# Powering.net
KiCad netlist of a schematic drawn in Altium Designer
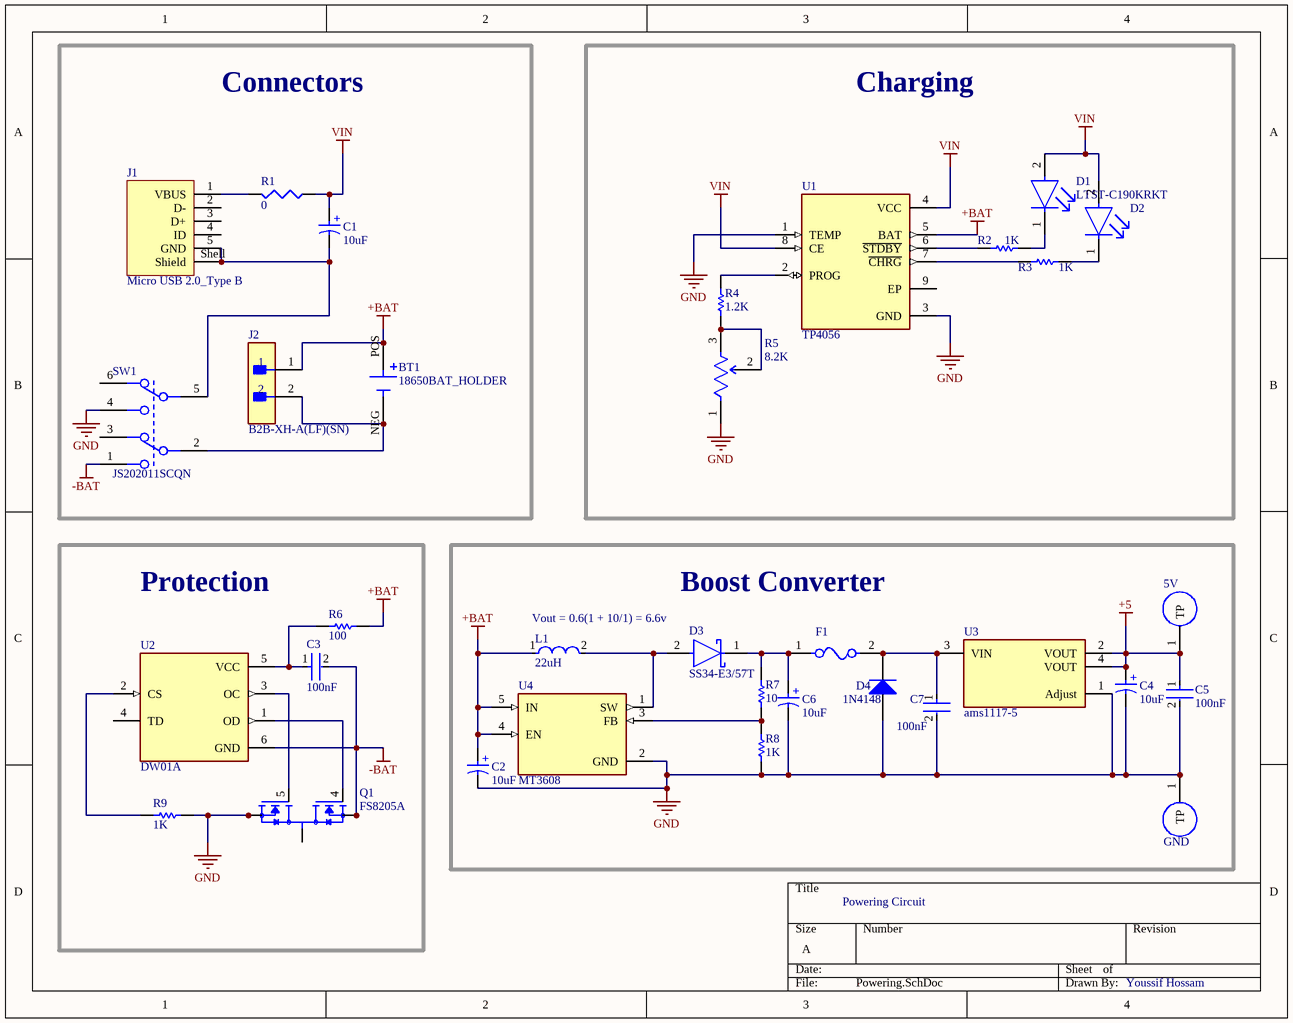
[diagram p0: Powering.SchDoc]

(export (version "E")
  (design (tool "Eeschema 10.0.6"))
  (components
    (comp (ref "5V")
      (value "Test Point")
      (footprint "Test_Point")
      (libsource (lib "YoussifLIB") (part "Test Point"))
    )
    (comp (ref "BT1")
      (value "18650BAT_HOLDER")
      (footprint "18650BAT_HOLDER")
      (description "Battery Holder (Open) 18650 1 Cell PC Pin")
      (fields (field (name "MP") "BK-18650-PC2"))
      (libsource (lib "YoussifLIB") (part "18650BAT_HOLDER"))
    )
    (comp (ref "C1")
      (value "10uF")
      (footprint "WCAP-ASLU_D3H5.5")
      (description "WCAP-ASLU Aluminum Electrolytic Capacitor, V-Chip, D4 x H5.5mm, 10uF, 6.3V")
      (fields
        (field (name "MANUFACTURER PART NUMBER") "865090140001")
        (field (name "MANUFACTURER") "Wurth Elektronik")
      )
      (libsource (lib "YoussifLIB") (part "WCAP-ASLU_D3H5.5"))
    )
    (comp (ref "C2")
      (value "10uF")
      (footprint "WCAP-ASLU_D3H5.5")
      (description "WCAP-ASLU Aluminum Electrolytic Capacitor, V-Chip, D4 x H5.5mm, 10uF, 6.3V")
      (fields
        (field (name "MANUFACTURER PART NUMBER") "865090140001")
        (field (name "MANUFACTURER") "Wurth Elektronik")
      )
      (libsource (lib "YoussifLIB") (part "WCAP-ASLU_D3H5.5"))
    )
    (comp (ref "C3")
      (value "100nF")
      (footprint "FP-C0402-BB-MFG")
      (description "CAP CER 0.1UF 10V X5R 0402")
      (fields (field (name "MANUFACTURER") "Kemet") (field (name "TOLERANCE") "0.1"))
      (libsource (lib "Altium Content Vault") (part "b4654b650e69147ec39a6b967a45e02"))
    )
    (comp (ref "C4")
      (value "10uF")
      (footprint "WCAP-ASLU_D3H5.5")
      (description "WCAP-ASLU Aluminum Electrolytic Capacitor, V-Chip, D4 x H5.5mm, 10uF, 6.3V")
      (fields
        (field (name "MANUFACTURER PART NUMBER") "865090140001")
        (field (name "MANUFACTURER") "Wurth Elektronik")
      )
      (libsource (lib "YoussifLIB") (part "WCAP-ASLU_D3H5.5"))
    )
    (comp (ref "C5")
      (value "100nF")
      (footprint "FP-CGA3E-0_3-0_1-IPC_A")
      (description "Cap Ceramic 100nF 50V X7R 10% Pad SMD 0603 +125°C Automotive T/R")
      (fields (field (name "TOLERANCE") "10%") (field (name "VOLTAGE") "50V"))
      (libsource (lib "Altium Content Vault") (part "b4654b650e69147ec39a6b967a45e02"))
    )
    (comp (ref "C6")
      (value "10uF")
      (footprint "WCAP-ASLU_D3H5.5")
      (description "WCAP-ASLU Aluminum Electrolytic Capacitor, V-Chip, D4 x H5.5mm, 10uF, 6.3V")
      (fields
        (field (name "MANUFACTURER PART NUMBER") "865090140001")
        (field (name "MANUFACTURER") "Wurth Elektronik")
      )
      (libsource (lib "YoussifLIB") (part "WCAP-ASLU_D3H5.5"))
    )
    (comp (ref "C7")
      (value "100nF")
      (footprint "FP-CGA3E-0_3-0_1-IPC_A")
      (description "Cap Ceramic 100nF 50V X7R 10% Pad SMD 0603 +125°C Automotive T/R")
      (fields (field (name "TOLERANCE") "10%") (field (name "VOLTAGE") "50V"))
      (libsource (lib "Altium Content Vault") (part "b4654b650e69147ec39a6b967a45e02"))
    )
    (comp (ref "D1")
      (value "LTST-C190KRKT")
      (footprint "FP-LTST-C190KRKT-MFG")
      (description "LED RED CLEAR CHIP SMD")
      (libsource (lib "Altium Content Vault") (part "8706943c75ba83719d021d2fdc84c58"))
    )
    (comp (ref "D2")
      (value "LTST-C190GKT")
      (footprint "FP-LTST-C190GKT-MFG")
      (description "LED GREEN CLEAR CHIP SMD")
      (fields (field (name "VOLTAGE") "2V"))
      (libsource (lib "Altium Content Vault") (part "8706943c75ba83719d021d2fdc84c58"))
    )
    (comp (ref "D3")
      (value "SS34-E3/57T")
      (footprint "FP-95402-MFG")
      (description "DIODE SCHOTTKY 40V 3A DO214AB")
      (fields
        (field (name "MANUFACTURER") "Vishay")
        (field (name "OCTOPART") "https://octopart.com/ss34-e3%2F57t-vishay-39552907")
      )
      (libsource (lib "Altium Content Vault") (part "1d6ec82d83fb6aee721767c19dac4b9"))
    )
    (comp (ref "D4")
      (value "1N4148")
      (footprint "DIOD-SOD123-2_V")
      (description "Fast Switching Diode, 100 V, 0.15 A, -65 to 150 degC, 2-Pin?SOD123, RoHS, Tape and Reel")
      (fields (field (name "MANUFACTURER") "DiodesIncorporated"))
      (libsource (lib "Altium Content Vault") (part "D-AK-2"))
    )
    (comp (ref "F1")
      (value "0154004.DR")
      (footprint "FP-0154-MFG")
      (description "FUSE BRD MNT 4A 125VAC/VDC 2SMD")
      (fields
        (field (name "MANUFACTURER") "Littelfuse")
        (field (name "OCTOPART") "https://octopart.com/0154004.dr-littelfuse-565861")
      )
      (libsource (lib "Altium Content Vault") (part "5bcf9b9f640e542cf0359d10258e979"))
    )
    (comp (ref "GND")
      (value "Test Point")
      (footprint "Test_Point")
      (libsource (lib "YoussifLIB") (part "Test Point"))
    )
    (comp (ref "J1")
      (value "Micro USB 2.0_Type B")
      (footprint "Micro USB 2.0_Type B")
      (libsource (lib "YoussifLIB") (part "Micro USB 2.0_Type B"))
    )
    (comp (ref "J2")
      (value "B2B-XH-A(LF)(SN)")
      (footprint "FP-B2B-XH-A_LF_SN-MFG")
      (description "CONN HEADER VERT 2POS 2.5MM")
      (libsource (lib "Altium Content Vault") (part "3bc925449376181038e59eaffc5286c"))
    )
    (comp (ref "L1")
      (value "22uH")
      (footprint "FP-IHLP-2525CZ-FP_2_413x3-MFG")
      (description "Commercial Inductors, Low DCR Series 22uH 2.9A 135mΩ 20%")
      (fields (field (name "TOLERANCE") "20%"))
      (libsource (lib "Altium Content Vault") (part "725321dda6339637d4d059423bc1c3c"))
    )
    (comp (ref "Q1")
      (value "FS8205A")
      (footprint "SOP65P640X120-8N")
      (fields (field (name "MF") "Fortune Semiconductor"))
      (libsource (lib "YoussifLIB") (part "FS8205A"))
    )
    (comp (ref "R1")
      (value "0")
      (footprint "J1-0603")
      (description "Resistor")
      (fields (field (name "PUBLISHER") "Altium Limited"))
      (libsource (lib "Miscellaneous+Devices") (part "Res3"))
    )
    (comp (ref "R2")
      (value "1K")
      (footprint "RESC1005X40X25NL05T10")
      (fields (field (name "MANUFACTURER") "Yageo / Phycomp") (field (name "PART NUMBER") "RC0402JR-070RL"))
      (libsource (lib "Altium Content Vault") (part "RES"))
    )
    (comp (ref "R3")
      (value "1K")
      (footprint "RESC1005X40X25NL05T10")
      (fields (field (name "MANUFACTURER") "Yageo / Phycomp") (field (name "PART NUMBER") "RC0402JR-070RL"))
      (libsource (lib "Altium Content Vault") (part "RES"))
    )
    (comp (ref "R4")
      (value "1.2K")
      (footprint "RESC1608X55X25ML10T15")
      (description "Chip Resistor, 0 Ohm, +/- 5%, 0.1 W, -55 to 155 degC, 0603 (1608 Metric), RoHS, Tape and Reel")
      (fields (field (name "TOLERANCE") "5%") (field (name "MANUFACTURER") "Yageo"))
      (libsource (lib "Altium Content Vault") (part "RES-2"))
    )
    (comp (ref "R5")
      (value "8.2K")
      (footprint "FP-TS53YL-MFG")
      (description "TRIMMER 10K OHM 0.25W GW TOP ADJ")
      (fields (field (name "TOLERANCE") "20%"))
      (libsource (lib "Altium Content Vault") (part "af6d6fb613c1f66b9b47f3e4c9350cb"))
    )
    (comp (ref "R6")
      (value "100")
      (footprint "RESC1005X40X25NL05T10")
      (fields (field (name "MANUFACTURER") "Yageo / Phycomp") (field (name "PART NUMBER") "RC0402JR-070RL"))
      (libsource (lib "Altium Content Vault") (part "RES"))
    )
    (comp (ref "R7")
      (value "10")
      (footprint "RESC1608X55X25ML10T15")
      (description "Chip Resistor, 0 Ohm, +/- 5%, 0.1 W, -55 to 155 degC, 0603 (1608 Metric), RoHS, Tape and Reel")
      (fields (field (name "TOLERANCE") "5%") (field (name "MANUFACTURER") "Yageo"))
      (libsource (lib "Altium Content Vault") (part "RES-2"))
    )
    (comp (ref "R8")
      (value "1K")
      (footprint "RESC1608X55X25ML10T15")
      (description "Chip Resistor, 0 Ohm, +/- 5%, 0.1 W, -55 to 155 degC, 0603 (1608 Metric), RoHS, Tape and Reel")
      (fields (field (name "TOLERANCE") "5%") (field (name "MANUFACTURER") "Yageo"))
      (libsource (lib "Altium Content Vault") (part "RES-2"))
    )
    (comp (ref "R9")
      (value "1K")
      (footprint "RESC1608X55X25ML10T15")
      (description "Chip Resistor, 0 Ohm, +/- 5%, 0.1 W, -55 to 155 degC, 0603 (1608 Metric), RoHS, Tape and Reel")
      (fields (field (name "TOLERANCE") "5%") (field (name "MANUFACTURER") "Yageo"))
      (libsource (lib "Altium Content Vault") (part "RES-2"))
    )
    (comp (ref "SW1")
      (value "JS202011SCQN")
      (footprint "FP-JS202011SCQN-MFG")
      (description "SWITCH SLIDE DPDT 300MA 6V")
      (libsource (lib "Altium Content Vault") (part "ac99ea1af431c19115f5225061c5c88"))
    )
    (comp (ref "U1")
      (value "TP4056")
      (footprint "TP4056")
      (description "Complete single cell Li-Ion battery with a constant current / constant voltage linear charger")
      (fields (field (name "MF") "NanJing Top Power ASIC Corp."))
      (libsource (lib "YoussifLIB") (part "TP4056"))
    )
    (comp (ref "U2")
      (value "DW01A")
      (footprint "SOT95P280X145-6N")
      (description "One Cell Lithium-ion/Polymer Battery Protection IC")
      (fields (field (name "MF") "Fortune Semiconductor"))
      (libsource (lib "YoussifLIB") (part "DW01A"))
    )
    (comp (ref "U3")
      (value "ams1117-5")
      (footprint "FP-ams1117-IPC_C")
      (description "1A LOW DROPOUT VOLTAGE REGULATOR")
      (libsource (lib "Altium Content Vault") (part "59ad430b93a2c51b3e6ee7c3b069677"))
    )
    (comp (ref "U4")
      (value "MT3608")
      (footprint "SOT95P280X145-6N")
      (description "High Efficiency 1.2MHz2A Step Up Converter")
      (fields (field (name "MF") "Aerosemi Technology Co., Ltd"))
      (libsource (lib "YoussifLIB") (part "MT3608"))
    )
  )
  (nets
    (net (code "1") (name "+5") (class "Default")
      (node (ref "5V") (pin "1") (pinfunction "TP_1") (pintype "passive"))
      (node (ref "C4") (pin "1") (pinfunction "P_1") (pintype "passive"))
      (node (ref "C5") (pin "1") (pinfunction "1_1") (pintype "passive"))
      (node (ref "U3") (pin "2") (pinfunction "VOUT_2") (pintype "passive"))
      (node (ref "U3") (pin "4") (pinfunction "VOUT_4") (pintype "passive"))
    )
    (net (code "2") (name "+BAT") (class "Default")
      (node (ref "BT1") (pin "POS") (pinfunction "POS_POS") (pintype "passive"))
      (node (ref "C2") (pin "1") (pinfunction "P_1") (pintype "passive"))
      (node (ref "J2") (pin "1") (pinfunction "1_1") (pintype "passive"))
      (node (ref "L1") (pin "1") (pinfunction "1_1") (pintype "passive"))
      (node (ref "R6") (pin "2") (pinfunction "2_2") (pintype "passive"))
      (node (ref "U1") (pin "5") (pinfunction "BAT_5") (pintype "output"))
      (node (ref "U4") (pin "4") (pinfunction "EN_4") (pintype "input"))
      (node (ref "U4") (pin "5") (pinfunction "IN_5") (pintype "input"))
    )
    (net (code "3") (name "-BAT") (class "Default")
      (node (ref "C3") (pin "2") (pinfunction "2_2") (pintype "passive"))
      (node (ref "Q1") (pin "2") (pinfunction "S1_2") (pintype "passive"))
      (node (ref "Q1") (pin "3") (pinfunction "S1_3") (pintype "passive"))
      (node (ref "SW1") (pin "1") (pinfunction "1_1") (pintype "passive"))
      (node (ref "U2") (pin "6") (pinfunction "GND_6") (pintype "power_in"))
    )
    (net (code "4") (name "GND") (class "Default")
      (node (ref "C2") (pin "2") (pinfunction "N_2") (pintype "passive"))
      (node (ref "C4") (pin "2") (pinfunction "N_2") (pintype "passive"))
      (node (ref "C5") (pin "2") (pinfunction "2_2") (pintype "passive"))
      (node (ref "C6") (pin "2") (pinfunction "N_2") (pintype "passive"))
      (node (ref "C7") (pin "2") (pinfunction "2_2") (pintype "passive"))
      (node (ref "D4") (pin "1") (pinfunction "A_1") (pintype "passive"))
      (node (ref "GND") (pin "1") (pinfunction "TP_1") (pintype "passive"))
      (node (ref "Q1") (pin "6") (pinfunction "S2_6") (pintype "passive"))
      (node (ref "Q1") (pin "7") (pinfunction "S2_7") (pintype "passive"))
      (node (ref "R5") (pin "1") (pinfunction "a_1") (pintype "passive"))
      (node (ref "R8") (pin "1") (pinfunction "1_1") (pintype "passive"))
      (node (ref "R9") (pin "2") (pinfunction "2_2") (pintype "passive"))
      (node (ref "SW1") (pin "4") (pinfunction "4_4") (pintype "passive"))
      (node (ref "U1") (pin "1") (pinfunction "TEMP_1") (pintype "input"))
      (node (ref "U1") (pin "3") (pinfunction "GND_3") (pintype "power_in"))
      (node (ref "U3") (pin "1") (pinfunction "Adjust_1") (pintype "passive"))
      (node (ref "U4") (pin "2") (pinfunction "GND_2") (pintype "power_in"))
    )
    (net (code "5") (name "Net-(BT1-PadNEG)") (class "Default")
      (node (ref "BT1") (pin "NEG") (pinfunction "NEG_NEG") (pintype "passive"))
      (node (ref "J2") (pin "2") (pinfunction "2_2") (pintype "passive"))
      (node (ref "SW1") (pin "2") (pinfunction "2_2") (pintype "passive"))
    )
    (net (code "6") (name "Net-(C1-N)") (class "Default")
      (node (ref "C1") (pin "2") (pinfunction "N_2") (pintype "passive"))
      (node (ref "J1") (pin "5") (pinfunction "GND_5") (pintype "passive"))
      (node (ref "J1") (pin "Shell") (pinfunction "Shield_Shell") (pintype "passive"))
      (node (ref "SW1") (pin "5") (pinfunction "5_5") (pintype "passive"))
    )
    (net (code "7") (name "Net-(C6-P)") (class "Default")
      (node (ref "C6") (pin "1") (pinfunction "P_1") (pintype "passive"))
      (node (ref "D3") (pin "1") (pinfunction "C_1") (pintype "passive"))
      (node (ref "F1") (pin "1") (pinfunction "1_1") (pintype "passive"))
      (node (ref "R7") (pin "2") (pinfunction "2_2") (pintype "passive"))
    )
    (net (code "8") (name "Net-(D1-C)") (class "Default")
      (node (ref "D1") (pin "1") (pinfunction "C_1") (pintype "passive"))
      (node (ref "R2") (pin "2") (pinfunction "2_2") (pintype "passive"))
    )
    (net (code "9") (name "Net-(D2-C)") (class "Default")
      (node (ref "D2") (pin "1") (pinfunction "C_1") (pintype "passive"))
      (node (ref "R3") (pin "2") (pinfunction "2_2") (pintype "passive"))
    )
    (net (code "10") (name "Net-(D3-A)") (class "Default")
      (node (ref "D3") (pin "2") (pinfunction "A_2") (pintype "passive"))
      (node (ref "L1") (pin "2") (pinfunction "2_2") (pintype "passive"))
      (node (ref "U4") (pin "1") (pinfunction "SW_1") (pintype "output"))
    )
    (net (code "11") (name "Net-(D4-K)") (class "Default")
      (node (ref "C7") (pin "1") (pinfunction "1_1") (pintype "passive"))
      (node (ref "D4") (pin "2") (pinfunction "K_2") (pintype "passive"))
      (node (ref "F1") (pin "2") (pinfunction "2_2") (pintype "passive"))
      (node (ref "U3") (pin "3") (pinfunction "VIN_3") (pintype "power_in"))
    )
    (net (code "12") (name "Net-(J1-VBUS)") (class "Default")
      (node (ref "J1") (pin "1") (pinfunction "VBUS_1") (pintype "passive"))
      (node (ref "R1") (pin "2") (pinfunction "2_2") (pintype "passive"))
    )
    (net (code "13") (name "Net-(Q1-D12-Pad1)") (class "Default")
      (node (ref "Q1") (pin "1") (pinfunction "D12_1") (pintype "passive"))
      (node (ref "Q1") (pin "8") (pinfunction "D12_8") (pintype "passive"))
    )
    (net (code "14") (name "Net-(Q1-G1)") (class "Default")
      (node (ref "Q1") (pin "4") (pinfunction "G1_4") (pintype "passive"))
      (node (ref "U2") (pin "1") (pinfunction "OD_1") (pintype "output"))
    )
    (net (code "15") (name "Net-(Q1-G2)") (class "Default")
      (node (ref "Q1") (pin "5") (pinfunction "G2_5") (pintype "passive"))
      (node (ref "U2") (pin "3") (pinfunction "OC_3") (pintype "output"))
    )
    (net (code "16") (name "Net-(R5-b)") (class "Default")
      (node (ref "R4") (pin "1") (pinfunction "1_1") (pintype "passive"))
      (node (ref "R5") (pin "2") (pinfunction "b_2") (pintype "passive"))
      (node (ref "R5") (pin "3") (pinfunction "c_3") (pintype "passive"))
    )
    (net (code "17") (name "Net-(U1-PROG)") (class "Default")
      (node (ref "R4") (pin "2") (pinfunction "2_2") (pintype "passive"))
      (node (ref "U1") (pin "2") (pinfunction "PROG_2") (pintype "bidirectional"))
    )
    (net (code "18") (name "Net-(U1-~{CHRG})") (class "Default")
      (node (ref "R3") (pin "1") (pinfunction "1_1") (pintype "passive"))
      (node (ref "U1") (pin "7") (pinfunction "~{CHRG}_7") (pintype "output"))
    )
    (net (code "19") (name "Net-(U1-~{STDBY})") (class "Default")
      (node (ref "R2") (pin "1") (pinfunction "1_1") (pintype "passive"))
      (node (ref "U1") (pin "6") (pinfunction "~{STDBY}_6") (pintype "output"))
    )
    (net (code "20") (name "Net-(U2-CS)") (class "Default")
      (node (ref "R9") (pin "1") (pinfunction "1_1") (pintype "passive"))
      (node (ref "U2") (pin "2") (pinfunction "CS_2") (pintype "input"))
    )
    (net (code "21") (name "Net-(U2-VCC)") (class "Default")
      (node (ref "C3") (pin "1") (pinfunction "1_1") (pintype "passive"))
      (node (ref "R6") (pin "1") (pinfunction "1_1") (pintype "passive"))
      (node (ref "U2") (pin "5") (pinfunction "VCC_5") (pintype "power_in"))
    )
    (net (code "22") (name "Net-(U4-FB)") (class "Default")
      (node (ref "R7") (pin "1") (pinfunction "1_1") (pintype "passive"))
      (node (ref "R8") (pin "2") (pinfunction "2_2") (pintype "passive"))
      (node (ref "U4") (pin "3") (pinfunction "FB_3") (pintype "input"))
    )
    (net (code "23") (name "VIN") (class "Default")
      (node (ref "C1") (pin "1") (pinfunction "P_1") (pintype "passive"))
      (node (ref "D1") (pin "2") (pinfunction "A_2") (pintype "passive"))
      (node (ref "D2") (pin "2") (pinfunction "A_2") (pintype "passive"))
      (node (ref "R1") (pin "1") (pinfunction "1_1") (pintype "passive"))
      (node (ref "U1") (pin "4") (pinfunction "VCC_4") (pintype "power_in"))
      (node (ref "U1") (pin "8") (pinfunction "CE_8") (pintype "input"))
    )
    (net (code "24") (name "unconnected-(J1-D+-Pad3)") (class "Default")
      (node (ref "J1") (pin "3") (pinfunction "D+_3") (pintype "passive"))
    )
    (net (code "25") (name "unconnected-(J1-D--Pad2)") (class "Default")
      (node (ref "J1") (pin "2") (pinfunction "D-_2") (pintype "passive"))
    )
    (net (code "26") (name "unconnected-(J1-ID-Pad4)") (class "Default")
      (node (ref "J1") (pin "4") (pinfunction "ID_4") (pintype "passive"))
    )
    (net (code "27") (name "unconnected-(SW1-Pad3)") (class "Default")
      (node (ref "SW1") (pin "3") (pinfunction "3_3") (pintype "passive"))
    )
    (net (code "28") (name "unconnected-(SW1-Pad6)") (class "Default")
      (node (ref "SW1") (pin "6") (pinfunction "6_6") (pintype "passive"))
    )
    (net (code "29") (name "unconnected-(U1-EP-Pad9)") (class "Default")
      (node (ref "U1") (pin "9") (pinfunction "EP_9") (pintype "passive"))
    )
    (net (code "30") (name "unconnected-(U2-TD-Pad4)") (class "Default")
      (node (ref "U2") (pin "4") (pinfunction "TD_4") (pintype "passive"))
    )
  )
)
